# V1_0.net
KiCad netlist of a schematic drawn in Altium Designer
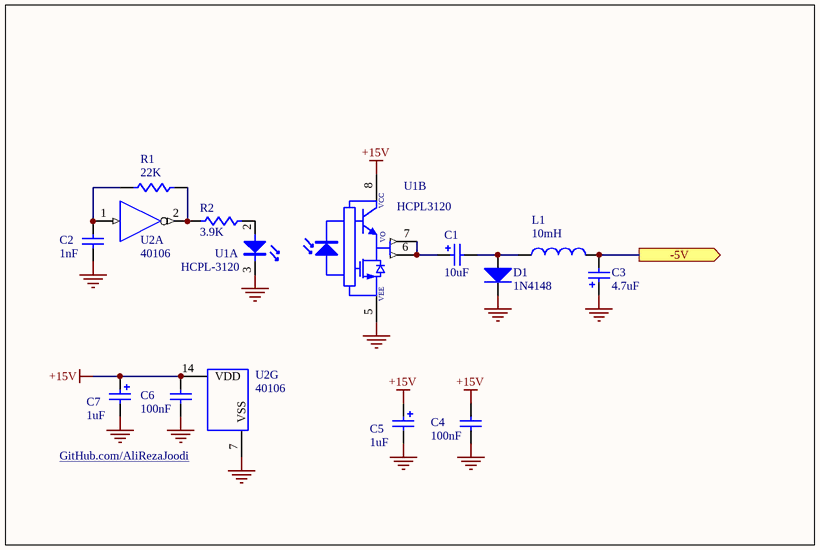
[diagram p0: V1.0.SchDoc]

(export (version "E")
  (design (tool "Eeschema 10.0.6"))
  (components
    (comp (ref "C1")
      (value "10uF")
      (footprint "CAPPR2.5-6.3x5")
      (description "Polarized Capacitor (Radial)")
      (fields
        (field (name "MANUFACTURER") "Generic Components")
        (field (name "Comment") "Cap Pol1")
        (field (name "PUBLISHER") "Altium Limited")
      )
      (libsource (lib "Miscellaneous Devices") (part "Cap Pol1"))
    )
    (comp (ref "C2")
      (value "1nF")
      (footprint "CAPNTO2.54-3.05x1.78A")
      (description "Capacitor")
      (fields
        (field (name "MANUFACTURER") "Generic Components")
        (field (name "Comment") "Cap")
        (field (name "PUBLISHER") "Altium Limited")
      )
      (libsource (lib "Miscellaneous Devices") (part "Cap"))
    )
    (comp (ref "C3")
      (value "4.7uF")
      (footprint "CAPPR2.5-6.3x5")
      (description "Polarized Capacitor (Radial)")
      (fields
        (field (name "MANUFACTURER") "Generic Components")
        (field (name "Comment") "Cap Pol1")
        (field (name "PUBLISHER") "Altium Limited")
      )
      (libsource (lib "Miscellaneous Devices") (part "Cap Pol1"))
    )
    (comp (ref "C4")
      (value "100nF")
      (footprint "CAPNTO2.54-3.05x1.78A")
      (description "Capacitor")
      (fields (field (name "MANUFACTURER") "Generic Components") (field (name "PUBLISHER") "Altium Limited"))
      (libsource (lib "Miscellaneous Devices") (part "Cap"))
    )
    (comp (ref "C5")
      (value "1uF")
      (footprint "CAPPR2.5-6.3x5")
      (description "Polarized Capacitor (Radial)")
      (fields (field (name "MANUFACTURER") "Generic Components") (field (name "PUBLISHER") "Altium Limited"))
      (libsource (lib "Miscellaneous Devices") (part "Cap Pol1"))
    )
    (comp (ref "C6")
      (value "100nF")
      (footprint "CAPNTO2.54-3.05x1.78A")
      (description "Capacitor")
      (fields (field (name "MANUFACTURER") "Generic Components") (field (name "PUBLISHER") "Altium Limited"))
      (libsource (lib "Miscellaneous Devices") (part "Cap"))
    )
    (comp (ref "C7")
      (value "1uF")
      (footprint "CAPPR2.5-6.3x5")
      (description "Polarized Capacitor (Radial)")
      (fields (field (name "MANUFACTURER") "Generic Components") (field (name "PUBLISHER") "Altium Limited"))
      (libsource (lib "Miscellaneous Devices") (part "Cap Pol1"))
    )
    (comp (ref "D1")
      (value "1N4148")
      (footprint "DIODE-0.4")
      (description "Default Diode")
      (fields
        (field (name "MANUFACTURER") "Generic Components")
        (field (name "Comment") "Diode")
        (field (name "PUBLISHER") "Altium Limited")
      )
      (libsource (lib "Miscellaneous Devices") (part "Diode"))
    )
    (comp (ref "L1")
      (value "10mH")
      (footprint "INDUCTOR-2V")
      (description "Inductor")
      (fields (field (name "PUBLISHER") "Altium Limited"))
      (libsource (lib "Miscellaneous Devices") (part "Inductor"))
    )
    (comp (ref "R1")
      (value "22K")
      (footprint "AXIAL-0.4")
      (description "Resistor")
      (fields (field (name "MANUFACTURER") "Generic Components") (field (name "PUBLISHER") "Altium Limited"))
      (libsource (lib "Miscellaneous Devices") (part "Res1"))
    )
    (comp (ref "R2")
      (value "3.9K")
      (footprint "AXIAL-0.4")
      (description "Resistor")
      (fields (field (name "MANUFACTURER") "Generic Components") (field (name "PUBLISHER") "Altium Limited"))
      (libsource (lib "Miscellaneous Devices") (part "Res1"))
    )
    (comp (ref "U1")
      (value "HCPL-3120")
      (footprint "DIP8")
      (libsource (lib "my Libraries") (part "HCPL-3120"))
    )
    (comp (ref "U2")
      (value "40106")
      (footprint "DIP14")
      (description "Hex inverting Schmitt trigger, 14-Pin")
      (fields (field (name "PUBLISHER") "Altium Limited"))
      (libsource (lib "my Libraries") (part "40106"))
    )
  )
  (nets
    (net (code "1") (name "+15V") (class "Default")
      (node (ref "C4") (pin "2") (pinfunction "2_2") (pintype "passive"))
      (node (ref "C5") (pin "1") (pinfunction "1_1") (pintype "passive"))
      (node (ref "C6") (pin "2") (pinfunction "2_2") (pintype "passive"))
      (node (ref "C7") (pin "1") (pinfunction "1_1") (pintype "passive"))
      (node (ref "U1") (pin "8") (pinfunction "VCC_8") (pintype "power_in"))
      (node (ref "U2") (pin "14") (pinfunction "VDD_14") (pintype "passive"))
    )
    (net (code "2") (name "/-5V") (class "Default")
      (node (ref "C3") (pin "2") (pinfunction "2_2") (pintype "passive"))
      (node (ref "L1") (pin "2") (pinfunction "2_2") (pintype "passive"))
    )
    (net (code "3") (name "GND") (class "Default")
      (node (ref "C2") (pin "2") (pinfunction "2_2") (pintype "passive"))
      (node (ref "C3") (pin "1") (pinfunction "1_1") (pintype "passive"))
      (node (ref "C4") (pin "1") (pinfunction "1_1") (pintype "passive"))
      (node (ref "C5") (pin "2") (pinfunction "2_2") (pintype "passive"))
      (node (ref "C6") (pin "1") (pinfunction "1_1") (pintype "passive"))
      (node (ref "C7") (pin "2") (pinfunction "2_2") (pintype "passive"))
      (node (ref "D1") (pin "2") (pinfunction "K_2") (pintype "passive"))
      (node (ref "U1") (pin "3") (pinfunction "K_3") (pintype "power_in"))
      (node (ref "U1") (pin "5") (pinfunction "VEE_5") (pintype "power_in"))
      (node (ref "U2") (pin "7") (pinfunction "VSS_7") (pintype "power_in"))
    )
    (net (code "4") (name "Net-(C1-Pad1)") (class "Default")
      (node (ref "C1") (pin "1") (pinfunction "1_1") (pintype "passive"))
      (node (ref "U1") (pin "6") (pinfunction "VO_6") (pintype "output"))
      (node (ref "U1") (pin "7") (pinfunction "VO_7") (pintype "output"))
    )
    (net (code "5") (name "Net-(D1-A)") (class "Default")
      (node (ref "C1") (pin "2") (pinfunction "2_2") (pintype "passive"))
      (node (ref "D1") (pin "1") (pinfunction "A_1") (pintype "passive"))
      (node (ref "L1") (pin "1") (pinfunction "1_1") (pintype "passive"))
    )
    (net (code "6") (name "Net-(U1A-A)") (class "Default")
      (node (ref "R2") (pin "2") (pinfunction "2_2") (pintype "passive"))
      (node (ref "U1") (pin "2") (pinfunction "A_2") (pintype "power_in"))
    )
    (net (code "7") (name "Net-(U2A-I)") (class "Default")
      (node (ref "C2") (pin "1") (pinfunction "1_1") (pintype "passive"))
      (node (ref "R1") (pin "2") (pinfunction "2_2") (pintype "passive"))
      (node (ref "U2") (pin "1") (pinfunction "I_1") (pintype "input"))
    )
    (net (code "8") (name "Net-(U2A-~{O})") (class "Default")
      (node (ref "R1") (pin "1") (pinfunction "1_1") (pintype "passive"))
      (node (ref "R2") (pin "1") (pinfunction "1_1") (pintype "passive"))
      (node (ref "U2") (pin "2") (pinfunction "~{O}_2") (pintype "output"))
    )
  )
)
